# pic_board.net
KiCad netlist of a schematic drawn in EAGLE
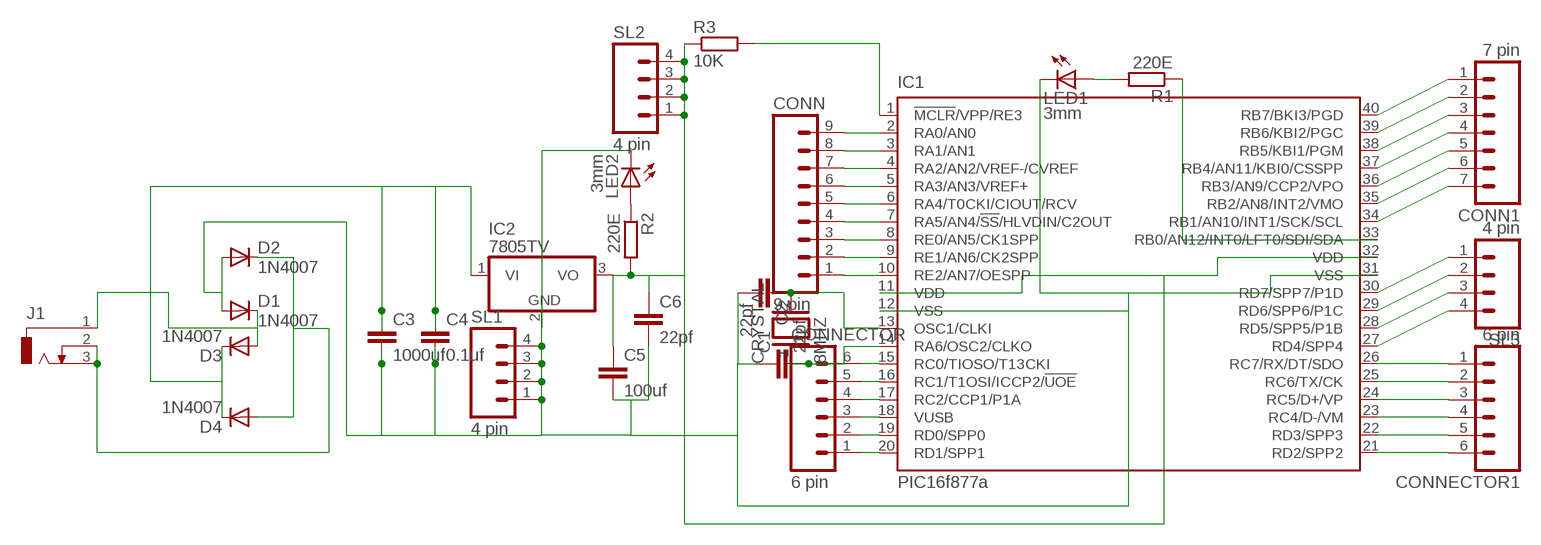
[diagram p0: schematic, sheet 1]

(export (version "E")
  (design (tool "Eeschema 10.0.6"))
  (components
    (comp (ref "C1")
      (value "22pf")
      (footprint "eagle-import:C2.5-2")
      (libsource (lib "eagle-import") (part "C2.5/2"))
    )
    (comp (ref "C2")
      (value "22pf")
      (footprint "eagle-import:C2.5-2")
      (libsource (lib "eagle-import") (part "C2.5/2"))
    )
    (comp (ref "C3")
      (value "1000uf")
      (footprint "eagle-import:C5B7.2")
      (libsource (lib "eagle-import") (part "C5/7.2"))
    )
    (comp (ref "C4")
      (value "0.1uf")
      (footprint "eagle-import:C2.5-3")
      (libsource (lib "eagle-import") (part "C2,5-3"))
    )
    (comp (ref "C5")
      (value "100uf")
      (footprint "eagle-import:C5B7.2")
      (libsource (lib "eagle-import") (part "C5/7.2"))
    )
    (comp (ref "C6")
      (value "22pf")
      (footprint "eagle-import:C2.5-2")
      (libsource (lib "eagle-import") (part "C2.5/2"))
    )
    (comp (ref "CONN")
      (value "9 pin")
      (footprint "eagle-import:09P")
      (libsource (lib "eagle-import") (part "M09"))
    )
    (comp (ref "CONN1")
      (value "7 pin")
      (footprint "eagle-import:07P")
      (libsource (lib "eagle-import") (part "M07"))
    )
    (comp (ref "CONNECTOR")
      (value "6 pin")
      (footprint "eagle-import:06P")
      (libsource (lib "eagle-import") (part "M06"))
    )
    (comp (ref "CONNECTOR1")
      (value "6 pin")
      (footprint "eagle-import:06P")
      (fields (field (name "OC_FARNELL") "unknown") (field (name "OC_NEWARK") "unknown"))
      (libsource (lib "eagle-import") (part "M06"))
    )
    (comp (ref "CRYSTAL")
      (value "8MHZ")
      (footprint "eagle-import:QS")
      (libsource (lib "eagle-import") (part "XTAL/S"))
    )
    (comp (ref "D1")
      (value "1N4007")
      (footprint "eagle-import:DO41-10")
      (libsource (lib "eagle-import") (part "1N4004"))
    )
    (comp (ref "D2")
      (value "1N4007")
      (footprint "eagle-import:DO41-10")
      (libsource (lib "eagle-import") (part "1N4004"))
    )
    (comp (ref "D3")
      (value "1N4007")
      (footprint "eagle-import:DO41-10")
      (libsource (lib "eagle-import") (part "1N4004"))
    )
    (comp (ref "D4")
      (value "1N4007")
      (footprint "eagle-import:DO41-10")
      (libsource (lib "eagle-import") (part "1N4004"))
    )
    (comp (ref "IC1")
      (value "PIC16f877a")
      (footprint "eagle-import:DIL40")
      (fields (field (name "MF") "MICROCHIP") (field (name "MPN") "PIC18F4455-I/P"))
      (libsource (lib "eagle-import") (part "PIC18F4_40455"))
    )
    (comp (ref "IC2")
      (value "7805TV")
      (footprint "eagle-import:TO220V")
      (libsource (lib "eagle-import") (part "78TV05"))
    )
    (comp (ref "J1")
      (value "DCJ0303")
      (footprint "eagle-import:DCJ0303")
      (libsource (lib "eagle-import") (part "DCJ0303"))
    )
    (comp (ref "LED1")
      (value "3mm")
      (footprint "eagle-import:LED3MM")
      (libsource (lib "eagle-import") (part "LED3MM"))
    )
    (comp (ref "LED2")
      (value "3mm")
      (footprint "eagle-import:LED3MM")
      (libsource (lib "eagle-import") (part "LED3MM"))
    )
    (comp (ref "R1")
      (value "220E")
      (footprint "eagle-import:0204_7")
      (libsource (lib "eagle-import") (part "R-EU_0204/7"))
    )
    (comp (ref "R2")
      (value "220E")
      (footprint "eagle-import:0204_7")
      (libsource (lib "eagle-import") (part "R-EU_0204/7"))
    )
    (comp (ref "R3")
      (value "10K")
      (footprint "eagle-import:0204_7")
      (libsource (lib "eagle-import") (part "R-EU_0204/7"))
    )
    (comp (ref "SL1")
      (value "4 pin")
      (footprint "eagle-import:04P")
      (libsource (lib "eagle-import") (part "M04"))
    )
    (comp (ref "SL2")
      (value "4 pin")
      (footprint "eagle-import:04P")
      (libsource (lib "eagle-import") (part "M04"))
    )
    (comp (ref "SL3")
      (value "4 pin")
      (footprint "eagle-import:04P")
      (fields (field (name "OC_FARNELL") "unknown") (field (name "OC_NEWARK") "unknown"))
      (libsource (lib "eagle-import") (part "M04"))
    )
  )
  (nets
    (net (code "1") (name "Net-(D1-PadC)") (class "Default")
      (node (ref "D1") (pin "C") (pinfunction "C_C") (pintype "passive"))
      (node (ref "D3") (pin "A") (pinfunction "A_A") (pintype "passive"))
      (node (ref "J1") (pin "1") (pinfunction "1_1") (pintype "passive"))
    )
    (net (code "2") (name "Net-(D2-PadC)") (class "Default")
      (node (ref "D2") (pin "C") (pinfunction "C_C") (pintype "passive"))
      (node (ref "D4") (pin "A") (pinfunction "A_A") (pintype "passive"))
      (node (ref "J1") (pin "2") (pinfunction "2_2") (pintype "passive"))
      (node (ref "J1") (pin "3") (pinfunction "3_3") (pintype "passive"))
    )
    (net (code "3") (name "Net-(IC1-OSC1{slash}CLKI)") (class "Default")
      (node (ref "C2") (pin "1") (pinfunction "1_1") (pintype "passive"))
      (node (ref "CRYSTAL") (pin "2") (pinfunction "2_2") (pintype "passive"))
      (node (ref "IC1") (pin "13") (pinfunction "OSC1/CLKI_13") (pintype "input"))
    )
    (net (code "4") (name "Net-(IC1-RA0{slash}AN0)") (class "Default")
      (node (ref "CONN") (pin "9") (pinfunction "9_9") (pintype "passive"))
      (node (ref "IC1") (pin "2") (pinfunction "RA0/AN0_2") (pintype "bidirectional"))
    )
    (net (code "5") (name "Net-(IC1-RA1{slash}AN1)") (class "Default")
      (node (ref "CONN") (pin "8") (pinfunction "8_8") (pintype "passive"))
      (node (ref "IC1") (pin "3") (pinfunction "RA1/AN1_3") (pintype "bidirectional"))
    )
    (net (code "6") (name "Net-(IC1-RA2{slash}AN2{slash}VREF-{slash}CVREF)") (class "Default")
      (node (ref "CONN") (pin "7") (pinfunction "7_7") (pintype "passive"))
      (node (ref "IC1") (pin "4") (pinfunction "RA2/AN2/VREF-/CVREF_4") (pintype "bidirectional"))
    )
    (net (code "7") (name "Net-(IC1-RA3{slash}AN3{slash}VREF+)") (class "Default")
      (node (ref "CONN") (pin "6") (pinfunction "6_6") (pintype "passive"))
      (node (ref "IC1") (pin "5") (pinfunction "RA3/AN3/VREF+_5") (pintype "bidirectional"))
    )
    (net (code "8") (name "Net-(IC1-RA4{slash}T0CKI{slash}CIOUT{slash}RCV)") (class "Default")
      (node (ref "CONN") (pin "5") (pinfunction "5_5") (pintype "passive"))
      (node (ref "IC1") (pin "6") (pinfunction "RA4/T0CKI/CIOUT/RCV_6") (pintype "bidirectional"))
    )
    (net (code "9") (name "Net-(IC1-RA5{slash}AN4{slash}~{SS}{slash}HLVDIN{slash}C2OUT)") (class "Default")
      (node (ref "CONN") (pin "4") (pinfunction "4_4") (pintype "passive"))
      (node (ref "IC1") (pin "7") (pinfunction "RA5/AN4/~{SS}/HLVDIN/C2OUT_7") (pintype "bidirectional"))
    )
    (net (code "10") (name "Net-(IC1-RA6{slash}OSC2{slash}CLKO)") (class "Default")
      (node (ref "C1") (pin "2") (pinfunction "2_2") (pintype "passive"))
      (node (ref "CRYSTAL") (pin "1") (pinfunction "1_1") (pintype "passive"))
      (node (ref "IC1") (pin "14") (pinfunction "RA6/OSC2/CLKO_14") (pintype "output"))
    )
    (net (code "11") (name "Net-(IC1-RB0{slash}AN12{slash}INT0{slash}LFT0{slash}SDI{slash}SDA)") (class "Default")
      (node (ref "IC1") (pin "33") (pinfunction "RB0/AN12/INT0/LFT0/SDI/SDA_33") (pintype "bidirectional"))
      (node (ref "R1") (pin "1") (pinfunction "1_1") (pintype "passive"))
    )
    (net (code "12") (name "Net-(IC1-RB1{slash}AN10{slash}INT1{slash}SCK{slash}SCL)") (class "Default")
      (node (ref "CONN1") (pin "7") (pinfunction "7_7") (pintype "passive"))
      (node (ref "IC1") (pin "34") (pinfunction "RB1/AN10/INT1/SCK/SCL_34") (pintype "bidirectional"))
    )
    (net (code "13") (name "Net-(IC1-RB2{slash}AN8{slash}INT2{slash}VMO)") (class "Default")
      (node (ref "CONN1") (pin "6") (pinfunction "6_6") (pintype "passive"))
      (node (ref "IC1") (pin "35") (pinfunction "RB2/AN8/INT2/VMO_35") (pintype "bidirectional"))
    )
    (net (code "14") (name "Net-(IC1-RB3{slash}AN9{slash}CCP2{slash}VPO)") (class "Default")
      (node (ref "CONN1") (pin "5") (pinfunction "5_5") (pintype "passive"))
      (node (ref "IC1") (pin "36") (pinfunction "RB3/AN9/CCP2/VPO_36") (pintype "bidirectional"))
    )
    (net (code "15") (name "Net-(IC1-RB4{slash}AN11{slash}KBI0{slash}CSSPP)") (class "Default")
      (node (ref "CONN1") (pin "4") (pinfunction "4_4") (pintype "passive"))
      (node (ref "IC1") (pin "37") (pinfunction "RB4/AN11/KBI0/CSSPP_37") (pintype "bidirectional"))
    )
    (net (code "16") (name "Net-(IC1-RB5{slash}KBI1{slash}PGM)") (class "Default")
      (node (ref "CONN1") (pin "3") (pinfunction "3_3") (pintype "passive"))
      (node (ref "IC1") (pin "38") (pinfunction "RB5/KBI1/PGM_38") (pintype "bidirectional"))
    )
    (net (code "17") (name "Net-(IC1-RB6{slash}KBI2{slash}PGC)") (class "Default")
      (node (ref "CONN1") (pin "2") (pinfunction "2_2") (pintype "passive"))
      (node (ref "IC1") (pin "39") (pinfunction "RB6/KBI2/PGC_39") (pintype "bidirectional"))
    )
    (net (code "18") (name "Net-(IC1-RB7{slash}BKI3{slash}PGD)") (class "Default")
      (node (ref "CONN1") (pin "1") (pinfunction "1_1") (pintype "passive"))
      (node (ref "IC1") (pin "40") (pinfunction "RB7/BKI3/PGD_40") (pintype "bidirectional"))
    )
    (net (code "19") (name "Net-(IC1-RC0{slash}TIOSO{slash}T13CKI)") (class "Default")
      (node (ref "CONNECTOR") (pin "6") (pinfunction "6_6") (pintype "passive"))
      (node (ref "IC1") (pin "15") (pinfunction "RC0/TIOSO/T13CKI_15") (pintype "bidirectional"))
    )
    (net (code "20") (name "Net-(IC1-RC1{slash}T1OSI{slash}ICCP2{slash}~{UOE})") (class "Default")
      (node (ref "CONNECTOR") (pin "5") (pinfunction "5_5") (pintype "passive"))
      (node (ref "IC1") (pin "16") (pinfunction "RC1/T1OSI/ICCP2/~{UOE}_16") (pintype "bidirectional"))
    )
    (net (code "21") (name "Net-(IC1-RC2{slash}CCP1{slash}P1A)") (class "Default")
      (node (ref "CONNECTOR") (pin "4") (pinfunction "4_4") (pintype "passive"))
      (node (ref "IC1") (pin "17") (pinfunction "RC2/CCP1/P1A_17") (pintype "bidirectional"))
    )
    (net (code "22") (name "Net-(IC1-RC4{slash}D-{slash}VM)") (class "Default")
      (node (ref "CONNECTOR1") (pin "4") (pinfunction "4_4") (pintype "passive"))
      (node (ref "IC1") (pin "23") (pinfunction "RC4/D-/VM_23") (pintype "bidirectional"))
    )
    (net (code "23") (name "Net-(IC1-RC5{slash}D+{slash}VP)") (class "Default")
      (node (ref "CONNECTOR1") (pin "3") (pinfunction "3_3") (pintype "passive"))
      (node (ref "IC1") (pin "24") (pinfunction "RC5/D+/VP_24") (pintype "bidirectional"))
    )
    (net (code "24") (name "Net-(IC1-RC6{slash}TX{slash}CK)") (class "Default")
      (node (ref "CONNECTOR1") (pin "2") (pinfunction "2_2") (pintype "passive"))
      (node (ref "IC1") (pin "25") (pinfunction "RC6/TX/CK_25") (pintype "bidirectional"))
    )
    (net (code "25") (name "Net-(IC1-RC7{slash}RX{slash}DT{slash}SDO)") (class "Default")
      (node (ref "CONNECTOR1") (pin "1") (pinfunction "1_1") (pintype "passive"))
      (node (ref "IC1") (pin "26") (pinfunction "RC7/RX/DT/SDO_26") (pintype "bidirectional"))
    )
    (net (code "26") (name "Net-(IC1-RD0{slash}SPP0)") (class "Default")
      (node (ref "CONNECTOR") (pin "2") (pinfunction "2_2") (pintype "passive"))
      (node (ref "IC1") (pin "19") (pinfunction "RD0/SPP0_19") (pintype "bidirectional"))
    )
    (net (code "27") (name "Net-(IC1-RD1{slash}SPP1)") (class "Default")
      (node (ref "CONNECTOR") (pin "1") (pinfunction "1_1") (pintype "passive"))
      (node (ref "IC1") (pin "20") (pinfunction "RD1/SPP1_20") (pintype "bidirectional"))
    )
    (net (code "28") (name "Net-(IC1-RD2{slash}SPP2)") (class "Default")
      (node (ref "CONNECTOR1") (pin "6") (pinfunction "6_6") (pintype "passive"))
      (node (ref "IC1") (pin "21") (pinfunction "RD2/SPP2_21") (pintype "bidirectional"))
    )
    (net (code "29") (name "Net-(IC1-RD3{slash}SPP3)") (class "Default")
      (node (ref "CONNECTOR1") (pin "5") (pinfunction "5_5") (pintype "passive"))
      (node (ref "IC1") (pin "22") (pinfunction "RD3/SPP3_22") (pintype "bidirectional"))
    )
    (net (code "30") (name "Net-(IC1-RD4{slash}SPP4)") (class "Default")
      (node (ref "IC1") (pin "27") (pinfunction "RD4/SPP4_27") (pintype "bidirectional"))
      (node (ref "SL3") (pin "4") (pinfunction "4_4") (pintype "passive"))
    )
    (net (code "31") (name "Net-(IC1-RD5{slash}SPP5{slash}P1B)") (class "Default")
      (node (ref "IC1") (pin "28") (pinfunction "RD5/SPP5/P1B_28") (pintype "bidirectional"))
      (node (ref "SL3") (pin "3") (pinfunction "3_3") (pintype "passive"))
    )
    (net (code "32") (name "Net-(IC1-RD6{slash}SPP6{slash}P1C)") (class "Default")
      (node (ref "IC1") (pin "29") (pinfunction "RD6/SPP6/P1C_29") (pintype "bidirectional"))
      (node (ref "SL3") (pin "2") (pinfunction "2_2") (pintype "passive"))
    )
    (net (code "33") (name "Net-(IC1-RD7{slash}SPP7{slash}P1D)") (class "Default")
      (node (ref "IC1") (pin "30") (pinfunction "RD7/SPP7/P1D_30") (pintype "bidirectional"))
      (node (ref "SL3") (pin "1") (pinfunction "1_1") (pintype "passive"))
    )
    (net (code "34") (name "Net-(IC1-RE0{slash}AN5{slash}CK1SPP)") (class "Default")
      (node (ref "CONN") (pin "3") (pinfunction "3_3") (pintype "passive"))
      (node (ref "IC1") (pin "8") (pinfunction "RE0/AN5/CK1SPP_8") (pintype "bidirectional"))
    )
    (net (code "35") (name "Net-(IC1-RE1{slash}AN6{slash}CK2SPP)") (class "Default")
      (node (ref "CONN") (pin "2") (pinfunction "2_2") (pintype "passive"))
      (node (ref "IC1") (pin "9") (pinfunction "RE1/AN6/CK2SPP_9") (pintype "bidirectional"))
    )
    (net (code "36") (name "Net-(IC1-RE2{slash}AN7{slash}OESPP)") (class "Default")
      (node (ref "CONN") (pin "1") (pinfunction "1_1") (pintype "passive"))
      (node (ref "IC1") (pin "10") (pinfunction "RE2/AN7/OESPP_10") (pintype "bidirectional"))
    )
    (net (code "37") (name "Net-(IC1-VUSB)") (class "Default")
      (node (ref "CONNECTOR") (pin "3") (pinfunction "3_3") (pintype "passive"))
      (node (ref "IC1") (pin "18") (pinfunction "VUSB_18") (pintype "bidirectional"))
    )
    (net (code "38") (name "Net-(IC1-~{MCLR}{slash}VPP{slash}RE3)") (class "Default")
      (node (ref "IC1") (pin "1") (pinfunction "~{MCLR}/VPP/RE3_1") (pintype "input"))
      (node (ref "R3") (pin "2") (pinfunction "2_2") (pintype "passive"))
    )
    (net (code "39") (name "Net-(IC2-GND)") (class "Default")
      (node (ref "C1") (pin "1") (pinfunction "1_1") (pintype "passive"))
      (node (ref "C2") (pin "2") (pinfunction "2_2") (pintype "passive"))
      (node (ref "C3") (pin "2") (pinfunction "2_2") (pintype "passive"))
      (node (ref "C4") (pin "2") (pinfunction "2_2") (pintype "passive"))
      (node (ref "C5") (pin "2") (pinfunction "2_2") (pintype "passive"))
      (node (ref "C6") (pin "2") (pinfunction "2_2") (pintype "passive"))
      (node (ref "D1") (pin "A") (pinfunction "A_A") (pintype "passive"))
      (node (ref "D2") (pin "A") (pinfunction "A_A") (pintype "passive"))
      (node (ref "IC1") (pin "12") (pinfunction "VSS_12") (pintype "power_in"))
      (node (ref "IC1") (pin "31") (pinfunction "VSS_31") (pintype "power_in"))
      (node (ref "IC2") (pin "2") (pinfunction "GND_2") (pintype "passive"))
      (node (ref "LED1") (pin "K") (pinfunction "C_K") (pintype "passive"))
      (node (ref "LED2") (pin "K") (pinfunction "C_K") (pintype "passive"))
      (node (ref "SL1") (pin "1") (pinfunction "1_1") (pintype "passive"))
      (node (ref "SL1") (pin "2") (pinfunction "2_2") (pintype "passive"))
      (node (ref "SL1") (pin "3") (pinfunction "3_3") (pintype "passive"))
      (node (ref "SL1") (pin "4") (pinfunction "4_4") (pintype "passive"))
    )
    (net (code "40") (name "Net-(IC2-VI)") (class "Default")
      (node (ref "C3") (pin "1") (pinfunction "1_1") (pintype "passive"))
      (node (ref "C4") (pin "1") (pinfunction "1_1") (pintype "passive"))
      (node (ref "D3") (pin "C") (pinfunction "C_C") (pintype "passive"))
      (node (ref "D4") (pin "C") (pinfunction "C_C") (pintype "passive"))
      (node (ref "IC2") (pin "1") (pinfunction "VI_1") (pintype "input"))
    )
    (net (code "41") (name "Net-(IC2-VO)") (class "Default")
      (node (ref "C5") (pin "1") (pinfunction "1_1") (pintype "passive"))
      (node (ref "C6") (pin "1") (pinfunction "1_1") (pintype "passive"))
      (node (ref "IC1") (pin "11") (pinfunction "VDD_11") (pintype "power_in"))
      (node (ref "IC1") (pin "32") (pinfunction "VDD_32") (pintype "power_in"))
      (node (ref "IC2") (pin "3") (pinfunction "VO_3") (pintype "passive"))
      (node (ref "R2") (pin "2") (pinfunction "2_2") (pintype "passive"))
      (node (ref "R3") (pin "1") (pinfunction "1_1") (pintype "passive"))
      (node (ref "SL2") (pin "1") (pinfunction "1_1") (pintype "passive"))
      (node (ref "SL2") (pin "2") (pinfunction "2_2") (pintype "passive"))
      (node (ref "SL2") (pin "3") (pinfunction "3_3") (pintype "passive"))
      (node (ref "SL2") (pin "4") (pinfunction "4_4") (pintype "passive"))
    )
    (net (code "42") (name "Net-(LED1-PadA)") (class "Default")
      (node (ref "LED1") (pin "A") (pinfunction "A_A") (pintype "passive"))
      (node (ref "R1") (pin "2") (pinfunction "2_2") (pintype "passive"))
    )
    (net (code "43") (name "Net-(LED2-PadA)") (class "Default")
      (node (ref "LED2") (pin "A") (pinfunction "A_A") (pintype "passive"))
      (node (ref "R2") (pin "1") (pinfunction "1_1") (pintype "passive"))
    )
  )
)
